# FET_drive.net
KiCad netlist of a schematic drawn in EAGLE
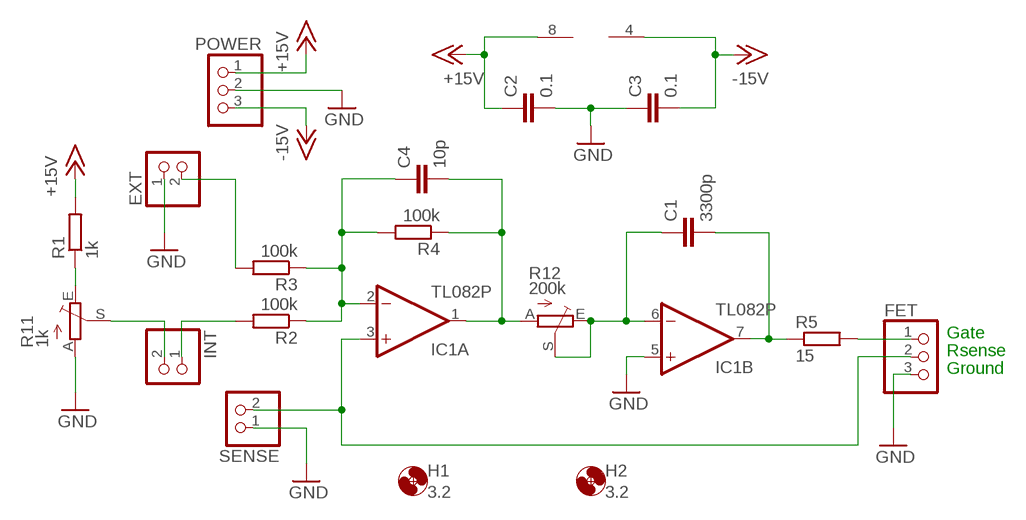
[diagram p0: schematic, sheet 1]

(export (version "E")
  (design (tool "Eeschema 10.0.6"))
  (components
    (comp (ref "C1")
      (value "3300p")
      (footprint "eagle-import:C025-025X050")
      (libsource (lib "eagle-import") (part "C-EU025-025X050"))
    )
    (comp (ref "C2")
      (value "0.1")
      (footprint "eagle-import:C025-025X050")
      (libsource (lib "eagle-import") (part "C-EU025-025X050"))
    )
    (comp (ref "C3")
      (value "0.1")
      (footprint "eagle-import:C025-025X050")
      (libsource (lib "eagle-import") (part "C-EU025-025X050"))
    )
    (comp (ref "C4")
      (value "10p")
      (footprint "eagle-import:C025-025X050")
      (libsource (lib "eagle-import") (part "C-EU025-025X050"))
    )
    (comp (ref "EXT")
      (value "PINHD-1X2")
      (footprint "eagle-import:1X02")
      (libsource (lib "eagle-import") (part "PINHD-1X2"))
    )
    (comp (ref "FET")
      (value "PINHD-1X3")
      (footprint "eagle-import:1X03")
      (libsource (lib "eagle-import") (part "PINHD-1X3"))
    )
    (comp (ref "H1")
      (value "3.2")
      (footprint "eagle-import:3,2")
      (libsource (lib "eagle-import") (part "MOUNT-HOLE3.2"))
    )
    (comp (ref "H2")
      (value "3.2")
      (footprint "eagle-import:3,2")
      (libsource (lib "eagle-import") (part "MOUNT-HOLE3.2"))
    )
    (comp (ref "IC1")
      (value "TL082P")
      (footprint "eagle-import:DIL08")
      (libsource (lib "eagle-import") (part "TL082P"))
    )
    (comp (ref "INT")
      (value "PINHD-1X2")
      (footprint "eagle-import:1X02")
      (libsource (lib "eagle-import") (part "PINHD-1X2"))
    )
    (comp (ref "POWER")
      (value "PINHD-1X3")
      (footprint "eagle-import:1X03")
      (libsource (lib "eagle-import") (part "PINHD-1X3"))
    )
    (comp (ref "R1")
      (value "1k")
      (footprint "eagle-import:R0805")
      (libsource (lib "eagle-import") (part "R-EU_R0805"))
    )
    (comp (ref "R2")
      (value "100k")
      (footprint "eagle-import:R0805")
      (libsource (lib "eagle-import") (part "R-EU_R0805"))
    )
    (comp (ref "R3")
      (value "100k")
      (footprint "eagle-import:R0805")
      (libsource (lib "eagle-import") (part "R-EU_R0805"))
    )
    (comp (ref "R4")
      (value "100k")
      (footprint "eagle-import:R0805")
      (libsource (lib "eagle-import") (part "R-EU_R0805"))
    )
    (comp (ref "R5")
      (value "15")
      (footprint "eagle-import:0204_5")
      (libsource (lib "eagle-import") (part "R-EU_0204/5"))
    )
    (comp (ref "R11")
      (value "1k")
      (footprint "eagle-import:B25P")
      (libsource (lib "eagle-import") (part "TRIM_EU-B25P"))
    )
    (comp (ref "R12")
      (value "200k")
      (footprint "eagle-import:B25P")
      (libsource (lib "eagle-import") (part "TRIM_EU-B25P"))
    )
    (comp (ref "SENSE")
      (value "PINHD-1X2")
      (footprint "eagle-import:1X02")
      (libsource (lib "eagle-import") (part "PINHD-1X2"))
    )
  )
  (nets
    (net (code "1") (name "+15V") (class "Default")
      (node (ref "C2") (pin "1") (pinfunction "1_1") (pintype "passive"))
      (node (ref "IC1") (pin "8") (pinfunction "V+_8") (pintype "power_in"))
      (node (ref "POWER") (pin "1") (pinfunction "1_1") (pintype "passive"))
      (node (ref "R1") (pin "2") (pinfunction "2_2") (pintype "passive"))
    )
    (net (code "2") (name "-15V") (class "Default")
      (node (ref "C3") (pin "2") (pinfunction "2_2") (pintype "passive"))
      (node (ref "IC1") (pin "4") (pinfunction "V-_4") (pintype "power_in"))
      (node (ref "POWER") (pin "3") (pinfunction "3_3") (pintype "passive"))
    )
    (net (code "3") (name "GND") (class "Default")
      (node (ref "C2") (pin "2") (pinfunction "2_2") (pintype "passive"))
      (node (ref "C3") (pin "1") (pinfunction "1_1") (pintype "passive"))
      (node (ref "EXT") (pin "1") (pinfunction "1_1") (pintype "passive"))
      (node (ref "FET") (pin "3") (pinfunction "3_3") (pintype "passive"))
      (node (ref "IC1") (pin "5") (pinfunction "+IN_5") (pintype "input"))
      (node (ref "POWER") (pin "2") (pinfunction "2_2") (pintype "passive"))
      (node (ref "R11") (pin "A") (pinfunction "A_A") (pintype "passive"))
      (node (ref "SENSE") (pin "1") (pinfunction "1_1") (pintype "passive"))
    )
    (net (code "4") (name "Net-(EXT-Pad2)") (class "Default")
      (node (ref "EXT") (pin "2") (pinfunction "2_2") (pintype "passive"))
      (node (ref "R3") (pin "2") (pinfunction "2_2") (pintype "passive"))
    )
    (net (code "5") (name "Net-(FET-Pad1)") (class "Default")
      (node (ref "FET") (pin "1") (pinfunction "1_1") (pintype "passive"))
      (node (ref "R5") (pin "2") (pinfunction "2_2") (pintype "passive"))
    )
    (net (code "6") (name "Net-(IC1A-+IN)") (class "Default")
      (node (ref "FET") (pin "2") (pinfunction "2_2") (pintype "passive"))
      (node (ref "IC1") (pin "3") (pinfunction "+IN_3") (pintype "input"))
      (node (ref "SENSE") (pin "2") (pinfunction "2_2") (pintype "passive"))
    )
    (net (code "7") (name "Net-(IC1A--IN)") (class "Default")
      (node (ref "C4") (pin "1") (pinfunction "1_1") (pintype "passive"))
      (node (ref "IC1") (pin "2") (pinfunction "-IN_2") (pintype "input"))
      (node (ref "R2") (pin "1") (pinfunction "1_1") (pintype "passive"))
      (node (ref "R3") (pin "1") (pinfunction "1_1") (pintype "passive"))
      (node (ref "R4") (pin "2") (pinfunction "2_2") (pintype "passive"))
    )
    (net (code "8") (name "Net-(IC1A-OUT)") (class "Default")
      (node (ref "C4") (pin "2") (pinfunction "2_2") (pintype "passive"))
      (node (ref "IC1") (pin "1") (pinfunction "OUT_1") (pintype "output"))
      (node (ref "R12") (pin "A") (pinfunction "A_A") (pintype "passive"))
      (node (ref "R4") (pin "1") (pinfunction "1_1") (pintype "passive"))
    )
    (net (code "9") (name "Net-(IC1B--IN)") (class "Default")
      (node (ref "C1") (pin "1") (pinfunction "1_1") (pintype "passive"))
      (node (ref "IC1") (pin "6") (pinfunction "-IN_6") (pintype "input"))
      (node (ref "R12") (pin "E") (pinfunction "E_E") (pintype "passive"))
      (node (ref "R12") (pin "S") (pinfunction "S_S") (pintype "passive"))
    )
    (net (code "10") (name "Net-(IC1B-OUT)") (class "Default")
      (node (ref "C1") (pin "2") (pinfunction "2_2") (pintype "passive"))
      (node (ref "IC1") (pin "7") (pinfunction "OUT_7") (pintype "output"))
      (node (ref "R5") (pin "1") (pinfunction "1_1") (pintype "passive"))
    )
    (net (code "11") (name "Net-(INT-Pad1)") (class "Default")
      (node (ref "INT") (pin "1") (pinfunction "1_1") (pintype "passive"))
      (node (ref "R2") (pin "2") (pinfunction "2_2") (pintype "passive"))
    )
    (net (code "12") (name "Net-(INT-Pad2)") (class "Default")
      (node (ref "INT") (pin "2") (pinfunction "2_2") (pintype "passive"))
      (node (ref "R11") (pin "S") (pinfunction "S_S") (pintype "passive"))
    )
    (net (code "13") (name "Net-(R1-Pad1)") (class "Default")
      (node (ref "R1") (pin "1") (pinfunction "1_1") (pintype "passive"))
      (node (ref "R11") (pin "E") (pinfunction "E_E") (pintype "passive"))
    )
  )
)
